# 0_1.net
KiCad netlist of a schematic drawn in Altium Designer
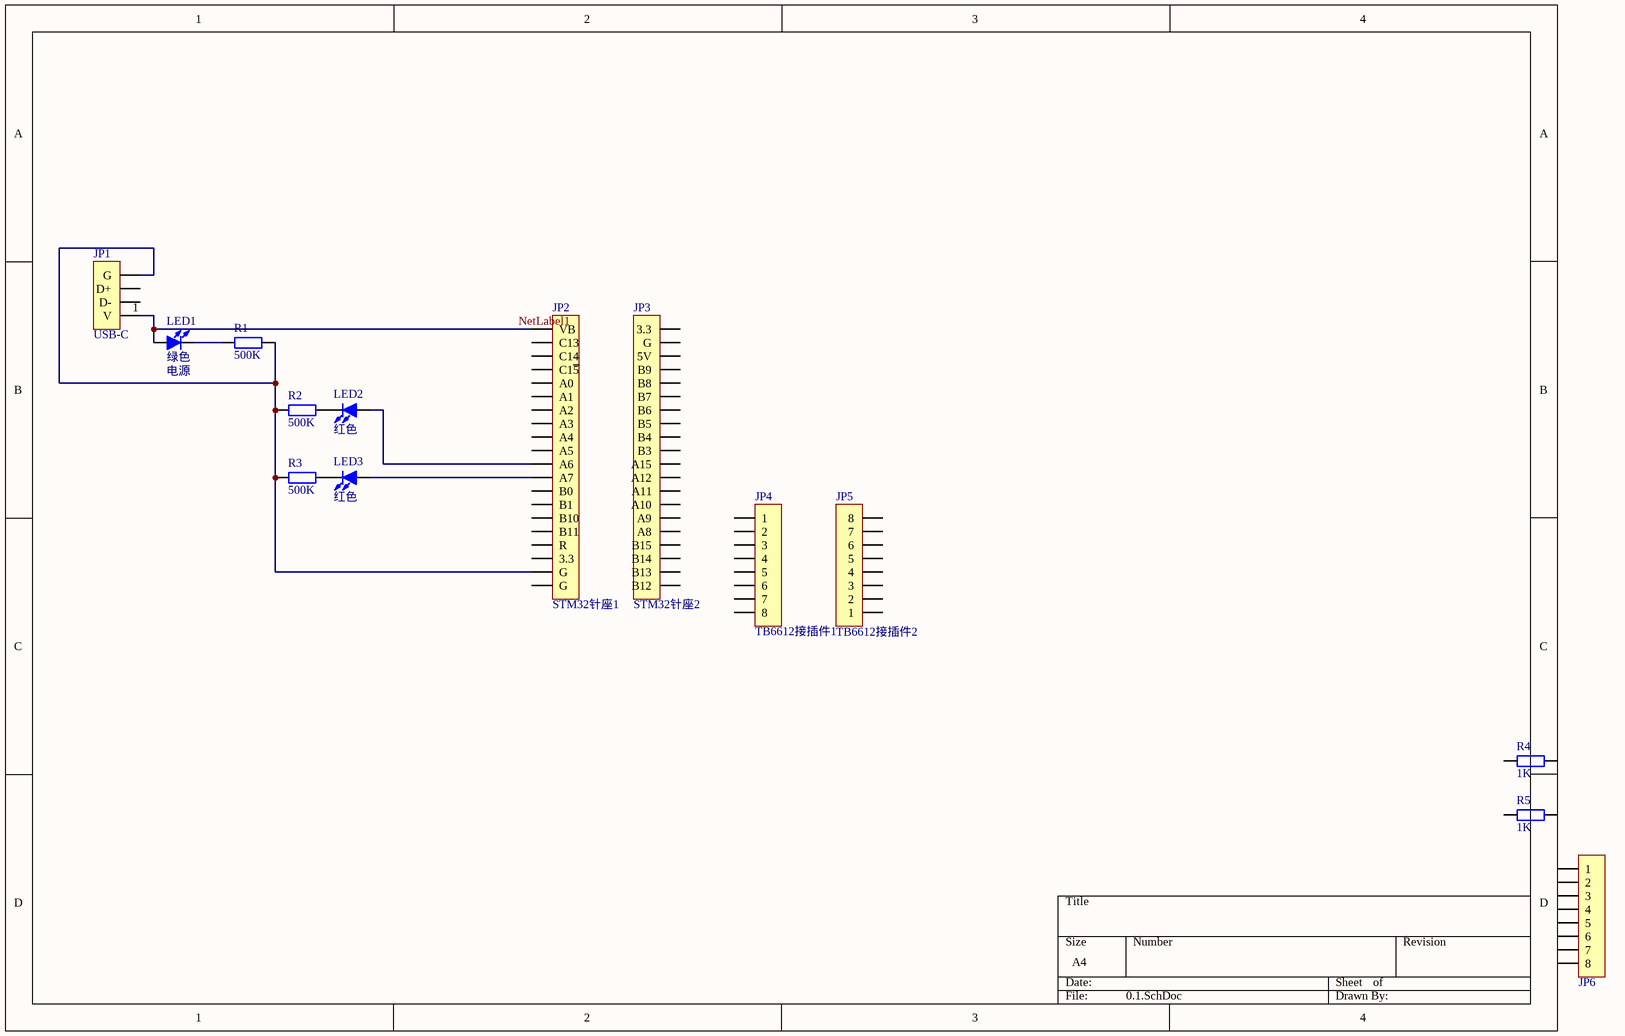
[diagram p0: 0.1.SchDoc]

(export (version "E")
  (design (tool "Eeschema 10.0.6"))
  (components
    (comp (ref "JP1")
      (value "HDR-1X4")
      (footprint "XH2.54-WI-4P")
      (description "4P接插件")
      (fields (field (name "BOM名称") "USB-C") (field (name "版权归属") "封装库来自淘宝 ID：黄晶宝石"))
      (libsource (lib "5.3 - 接插件-脚距2.54 (100mil) ") (part "Header 4"))
    )
    (comp (ref "JP2")
      (value "HDR-1X20")
      (footprint "HDR2.54-LI-20P")
      (description "20P接插件")
      (fields (field (name "BOM名称") "STM32针座1") (field (name "版权归属") "封装库来自淘宝 ID：黄晶宝石"))
      (libsource (lib "5.3 - 接插件-脚距2.54 (100mil) ") (part "Header 20"))
    )
    (comp (ref "JP3")
      (value "HDR-1X20")
      (footprint "HDR2.54-LI-20P")
      (description "20P接插件")
      (fields (field (name "BOM名称") "STM32针座2") (field (name "版权归属") "封装库来自淘宝 ID：黄晶宝石"))
      (libsource (lib "") (part "Header 20_1"))
    )
    (comp (ref "JP4")
      (value "HDR-1X8")
      (footprint "XH2.54-WI-8P")
      (description "8P接插件")
      (fields (field (name "BOM名称") "TB6612接插件1") (field (name "版权归属") "封装库来自淘宝 ID：黄晶宝石"))
      (libsource (lib "5.3 - 接插件-脚距2.54 (100mil) ") (part "Header 8"))
    )
    (comp (ref "JP5")
      (value "HDR-1X8")
      (footprint "XH2.54-WI-8P")
      (description "8P接插件")
      (fields (field (name "BOM名称") "TB6612接插件2") (field (name "版权归属") "封装库来自淘宝 ID：黄晶宝石"))
      (libsource (lib "") (part "Header 8_1"))
    )
    (comp (ref "JP6")
      (value "HDR-1X8")
      (footprint "XH2.54-WI-8P")
      (description "8P接插件")
      (fields (field (name "版权归属") "封装库来自淘宝 ID：黄晶宝石"))
      (libsource (lib "5.3 - 接插件-脚距2.54 (100mil) ") (part "Header 8"))
    )
    (comp (ref "LED1")
      (value "绿色")
      (footprint "LED 0805G")
      (description "贴片LED")
      (fields (field (name "BOM名称") "电源") (field (name "版权归属") "源创客"))
      (libsource (lib "LED") (part "LED-SMD"))
    )
    (comp (ref "LED2")
      (value "红色")
      (footprint "LED 0805G")
      (description "贴片LED")
      (fields (field (name "版权归属") "源创客"))
      (libsource (lib "LED") (part "LED-SMD"))
    )
    (comp (ref "LED3")
      (value "红色")
      (footprint "LED 0805G")
      (description "贴片LED")
      (fields (field (name "版权归属") "源创客"))
      (libsource (lib "LED") (part "LED-SMD"))
    )
    (comp (ref "R1")
      (value "500K")
      (footprint "R 0805_L")
      (description "贴片电阻")
      (fields (field (name "版权归属") "来自淘宝 ID：黄晶宝石"))
      (libsource (lib "0.1 - 电阻-电容-电感") (part "R"))
    )
    (comp (ref "R2")
      (value "500K")
      (footprint "R 0805_L")
      (description "贴片电阻")
      (fields (field (name "版权归属") "来自淘宝 ID：黄晶宝石"))
      (libsource (lib "0.1 - 电阻-电容-电感") (part "R"))
    )
    (comp (ref "R3")
      (value "500K")
      (footprint "R 0805_L")
      (description "贴片电阻")
      (fields (field (name "版权归属") "来自淘宝 ID：黄晶宝石"))
      (libsource (lib "0.1 - 电阻-电容-电感") (part "R"))
    )
    (comp (ref "R4")
      (value "1K")
      (footprint "R 0805")
      (description "贴片电阻")
      (fields (field (name "版权归属") "源创客"))
      (libsource (lib "电阻-电容-电感") (part "R"))
    )
    (comp (ref "R5")
      (value "1K")
      (footprint "R 0805")
      (description "贴片电阻")
      (fields (field (name "版权归属") "源创客"))
      (libsource (lib "电阻-电容-电感") (part "R"))
    )
  )
  (nets
    (net (code "1") (name "/NetLabel1") (class "Default")
      (node (ref "JP1") (pin "1") (pinfunction "V_1") (pintype "passive"))
      (node (ref "JP2") (pin "1") (pinfunction "VB_1") (pintype "passive"))
      (node (ref "LED1") (pin "1") (pinfunction "A_1") (pintype "passive"))
    )
    (net (code "2") (name "Net-(JP1-G)") (class "Default")
      (node (ref "JP1") (pin "4") (pinfunction "G_4") (pintype "passive"))
      (node (ref "JP2") (pin "19") (pinfunction "G_19") (pintype "passive"))
      (node (ref "R1") (pin "2") (pinfunction "2_2") (pintype "passive"))
      (node (ref "R2") (pin "2") (pinfunction "2_2") (pintype "passive"))
      (node (ref "R3") (pin "2") (pinfunction "2_2") (pintype "passive"))
    )
    (net (code "3") (name "Net-(JP2-A6)") (class "Default")
      (node (ref "JP2") (pin "11") (pinfunction "A6_11") (pintype "passive"))
      (node (ref "LED2") (pin "1") (pinfunction "A_1") (pintype "passive"))
    )
    (net (code "4") (name "Net-(JP2-A7)") (class "Default")
      (node (ref "JP2") (pin "12") (pinfunction "A7_12") (pintype "passive"))
      (node (ref "LED3") (pin "1") (pinfunction "A_1") (pintype "passive"))
    )
    (net (code "5") (name "Net-(LED1-K)") (class "Default")
      (node (ref "LED1") (pin "2") (pinfunction "K_2") (pintype "passive"))
      (node (ref "R1") (pin "1") (pinfunction "1_1") (pintype "passive"))
    )
    (net (code "6") (name "Net-(LED2-K)") (class "Default")
      (node (ref "LED2") (pin "2") (pinfunction "K_2") (pintype "passive"))
      (node (ref "R2") (pin "1") (pinfunction "1_1") (pintype "passive"))
    )
    (net (code "7") (name "Net-(LED3-K)") (class "Default")
      (node (ref "LED3") (pin "2") (pinfunction "K_2") (pintype "passive"))
      (node (ref "R3") (pin "1") (pinfunction "1_1") (pintype "passive"))
    )
    (net (code "8") (name "unconnected-(JP1-D+-Pad3)") (class "Default")
      (node (ref "JP1") (pin "3") (pinfunction "D+_3") (pintype "passive"))
    )
    (net (code "9") (name "unconnected-(JP1-D--Pad2)") (class "Default")
      (node (ref "JP1") (pin "2") (pinfunction "D-_2") (pintype "passive"))
    )
    (net (code "10") (name "unconnected-(JP2-3.3-Pad18)") (class "Default")
      (node (ref "JP2") (pin "18") (pinfunction "3.3_18") (pintype "passive"))
    )
    (net (code "11") (name "unconnected-(JP2-A0-Pad5)") (class "Default")
      (node (ref "JP2") (pin "5") (pinfunction "A0_5") (pintype "passive"))
    )
    (net (code "12") (name "unconnected-(JP2-A1-Pad6)") (class "Default")
      (node (ref "JP2") (pin "6") (pinfunction "A1_6") (pintype "passive"))
    )
    (net (code "13") (name "unconnected-(JP2-A2-Pad7)") (class "Default")
      (node (ref "JP2") (pin "7") (pinfunction "A2_7") (pintype "passive"))
    )
    (net (code "14") (name "unconnected-(JP2-A3-Pad8)") (class "Default")
      (node (ref "JP2") (pin "8") (pinfunction "A3_8") (pintype "passive"))
    )
    (net (code "15") (name "unconnected-(JP2-A4-Pad9)") (class "Default")
      (node (ref "JP2") (pin "9") (pinfunction "A4_9") (pintype "passive"))
    )
    (net (code "16") (name "unconnected-(JP2-A5-Pad10)") (class "Default")
      (node (ref "JP2") (pin "10") (pinfunction "A5_10") (pintype "passive"))
    )
    (net (code "17") (name "unconnected-(JP2-B0-Pad13)") (class "Default")
      (node (ref "JP2") (pin "13") (pinfunction "B0_13") (pintype "passive"))
    )
    (net (code "18") (name "unconnected-(JP2-B1-Pad14)") (class "Default")
      (node (ref "JP2") (pin "14") (pinfunction "B1_14") (pintype "passive"))
    )
    (net (code "19") (name "unconnected-(JP2-B10-Pad15)") (class "Default")
      (node (ref "JP2") (pin "15") (pinfunction "B10_15") (pintype "passive"))
    )
    (net (code "20") (name "unconnected-(JP2-B11-Pad16)") (class "Default")
      (node (ref "JP2") (pin "16") (pinfunction "B11_16") (pintype "passive"))
    )
    (net (code "21") (name "unconnected-(JP2-C1~{5}-Pad4)") (class "Default")
      (node (ref "JP2") (pin "4") (pinfunction "C1~{5}_4") (pintype "passive"))
    )
    (net (code "22") (name "unconnected-(JP2-C13-Pad2)") (class "Default")
      (node (ref "JP2") (pin "2") (pinfunction "C13_2") (pintype "passive"))
    )
    (net (code "23") (name "unconnected-(JP2-C14-Pad3)") (class "Default")
      (node (ref "JP2") (pin "3") (pinfunction "C14_3") (pintype "passive"))
    )
    (net (code "24") (name "unconnected-(JP2-G-Pad20)") (class "Default")
      (node (ref "JP2") (pin "20") (pinfunction "G_20") (pintype "passive"))
    )
    (net (code "25") (name "unconnected-(JP2-R-Pad17)") (class "Default")
      (node (ref "JP2") (pin "17") (pinfunction "R_17") (pintype "passive"))
    )
    (net (code "26") (name "unconnected-(JP3-3.3-Pad20)") (class "Default")
      (node (ref "JP3") (pin "20") (pinfunction "3.3_20") (pintype "passive"))
    )
    (net (code "27") (name "unconnected-(JP3-5V-Pad18)") (class "Default")
      (node (ref "JP3") (pin "18") (pinfunction "5V_18") (pintype "passive"))
    )
    (net (code "28") (name "unconnected-(JP3-A8-Pad5)") (class "Default")
      (node (ref "JP3") (pin "5") (pinfunction "A8_5") (pintype "passive"))
    )
    (net (code "29") (name "unconnected-(JP3-A9-Pad6)") (class "Default")
      (node (ref "JP3") (pin "6") (pinfunction "A9_6") (pintype "passive"))
    )
    (net (code "30") (name "unconnected-(JP3-A10-Pad7)") (class "Default")
      (node (ref "JP3") (pin "7") (pinfunction "A10_7") (pintype "passive"))
    )
    (net (code "31") (name "unconnected-(JP3-A11-Pad8)") (class "Default")
      (node (ref "JP3") (pin "8") (pinfunction "A11_8") (pintype "passive"))
    )
    (net (code "32") (name "unconnected-(JP3-A12-Pad9)") (class "Default")
      (node (ref "JP3") (pin "9") (pinfunction "A12_9") (pintype "passive"))
    )
    (net (code "33") (name "unconnected-(JP3-A15-Pad10)") (class "Default")
      (node (ref "JP3") (pin "10") (pinfunction "A15_10") (pintype "passive"))
    )
    (net (code "34") (name "unconnected-(JP3-B3-Pad11)") (class "Default")
      (node (ref "JP3") (pin "11") (pinfunction "B3_11") (pintype "passive"))
    )
    (net (code "35") (name "unconnected-(JP3-B4-Pad12)") (class "Default")
      (node (ref "JP3") (pin "12") (pinfunction "B4_12") (pintype "passive"))
    )
    (net (code "36") (name "unconnected-(JP3-B5-Pad13)") (class "Default")
      (node (ref "JP3") (pin "13") (pinfunction "B5_13") (pintype "passive"))
    )
    (net (code "37") (name "unconnected-(JP3-B6-Pad14)") (class "Default")
      (node (ref "JP3") (pin "14") (pinfunction "B6_14") (pintype "passive"))
    )
    (net (code "38") (name "unconnected-(JP3-B7-Pad15)") (class "Default")
      (node (ref "JP3") (pin "15") (pinfunction "B7_15") (pintype "passive"))
    )
    (net (code "39") (name "unconnected-(JP3-B8-Pad16)") (class "Default")
      (node (ref "JP3") (pin "16") (pinfunction "B8_16") (pintype "passive"))
    )
    (net (code "40") (name "unconnected-(JP3-B9-Pad17)") (class "Default")
      (node (ref "JP3") (pin "17") (pinfunction "B9_17") (pintype "passive"))
    )
    (net (code "41") (name "unconnected-(JP3-B12-Pad1)") (class "Default")
      (node (ref "JP3") (pin "1") (pinfunction "B12_1") (pintype "passive"))
    )
    (net (code "42") (name "unconnected-(JP3-B13-Pad2)") (class "Default")
      (node (ref "JP3") (pin "2") (pinfunction "B13_2") (pintype "passive"))
    )
    (net (code "43") (name "unconnected-(JP3-B14-Pad3)") (class "Default")
      (node (ref "JP3") (pin "3") (pinfunction "B14_3") (pintype "passive"))
    )
    (net (code "44") (name "unconnected-(JP3-B15-Pad4)") (class "Default")
      (node (ref "JP3") (pin "4") (pinfunction "B15_4") (pintype "passive"))
    )
    (net (code "45") (name "unconnected-(JP3-G-Pad19)") (class "Default")
      (node (ref "JP3") (pin "19") (pinfunction "G_19") (pintype "passive"))
    )
    (net (code "46") (name "unconnected-(JP4-Pad1)") (class "Default")
      (node (ref "JP4") (pin "1") (pinfunction "1_1") (pintype "passive"))
    )
    (net (code "47") (name "unconnected-(JP4-Pad2)") (class "Default")
      (node (ref "JP4") (pin "2") (pinfunction "2_2") (pintype "passive"))
    )
    (net (code "48") (name "unconnected-(JP4-Pad3)") (class "Default")
      (node (ref "JP4") (pin "3") (pinfunction "3_3") (pintype "passive"))
    )
    (net (code "49") (name "unconnected-(JP4-Pad4)") (class "Default")
      (node (ref "JP4") (pin "4") (pinfunction "4_4") (pintype "passive"))
    )
    (net (code "50") (name "unconnected-(JP4-Pad5)") (class "Default")
      (node (ref "JP4") (pin "5") (pinfunction "5_5") (pintype "passive"))
    )
    (net (code "51") (name "unconnected-(JP4-Pad6)") (class "Default")
      (node (ref "JP4") (pin "6") (pinfunction "6_6") (pintype "passive"))
    )
    (net (code "52") (name "unconnected-(JP4-Pad7)") (class "Default")
      (node (ref "JP4") (pin "7") (pinfunction "7_7") (pintype "passive"))
    )
    (net (code "53") (name "unconnected-(JP4-Pad8)") (class "Default")
      (node (ref "JP4") (pin "8") (pinfunction "8_8") (pintype "passive"))
    )
    (net (code "54") (name "unconnected-(JP5-Pad1)") (class "Default")
      (node (ref "JP5") (pin "1") (pinfunction "1_1") (pintype "passive"))
    )
    (net (code "55") (name "unconnected-(JP5-Pad2)") (class "Default")
      (node (ref "JP5") (pin "2") (pinfunction "2_2") (pintype "passive"))
    )
    (net (code "56") (name "unconnected-(JP5-Pad3)") (class "Default")
      (node (ref "JP5") (pin "3") (pinfunction "3_3") (pintype "passive"))
    )
    (net (code "57") (name "unconnected-(JP5-Pad4)") (class "Default")
      (node (ref "JP5") (pin "4") (pinfunction "4_4") (pintype "passive"))
    )
    (net (code "58") (name "unconnected-(JP5-Pad5)") (class "Default")
      (node (ref "JP5") (pin "5") (pinfunction "5_5") (pintype "passive"))
    )
    (net (code "59") (name "unconnected-(JP5-Pad6)") (class "Default")
      (node (ref "JP5") (pin "6") (pinfunction "6_6") (pintype "passive"))
    )
    (net (code "60") (name "unconnected-(JP5-Pad7)") (class "Default")
      (node (ref "JP5") (pin "7") (pinfunction "7_7") (pintype "passive"))
    )
    (net (code "61") (name "unconnected-(JP5-Pad8)") (class "Default")
      (node (ref "JP5") (pin "8") (pinfunction "8_8") (pintype "passive"))
    )
    (net (code "62") (name "unconnected-(JP6-Pad1)") (class "Default")
      (node (ref "JP6") (pin "1") (pinfunction "1_1") (pintype "passive"))
    )
    (net (code "63") (name "unconnected-(JP6-Pad2)") (class "Default")
      (node (ref "JP6") (pin "2") (pinfunction "2_2") (pintype "passive"))
    )
    (net (code "64") (name "unconnected-(JP6-Pad3)") (class "Default")
      (node (ref "JP6") (pin "3") (pinfunction "3_3") (pintype "passive"))
    )
    (net (code "65") (name "unconnected-(JP6-Pad4)") (class "Default")
      (node (ref "JP6") (pin "4") (pinfunction "4_4") (pintype "passive"))
    )
    (net (code "66") (name "unconnected-(JP6-Pad5)") (class "Default")
      (node (ref "JP6") (pin "5") (pinfunction "5_5") (pintype "passive"))
    )
    (net (code "67") (name "unconnected-(JP6-Pad6)") (class "Default")
      (node (ref "JP6") (pin "6") (pinfunction "6_6") (pintype "passive"))
    )
    (net (code "68") (name "unconnected-(JP6-Pad7)") (class "Default")
      (node (ref "JP6") (pin "7") (pinfunction "7_7") (pintype "passive"))
    )
    (net (code "69") (name "unconnected-(JP6-Pad8)") (class "Default")
      (node (ref "JP6") (pin "8") (pinfunction "8_8") (pintype "passive"))
    )
    (net (code "70") (name "unconnected-(R4-Pad1)") (class "Default")
      (node (ref "R4") (pin "1") (pinfunction "1_1") (pintype "passive"))
    )
    (net (code "71") (name "unconnected-(R4-Pad2)") (class "Default")
      (node (ref "R4") (pin "2") (pinfunction "2_2") (pintype "passive"))
    )
    (net (code "72") (name "unconnected-(R5-Pad1)") (class "Default")
      (node (ref "R5") (pin "1") (pinfunction "1_1") (pintype "passive"))
    )
    (net (code "73") (name "unconnected-(R5-Pad2)") (class "Default")
      (node (ref "R5") (pin "2") (pinfunction "2_2") (pintype "passive"))
    )
  )
)
